# 5ButtonSwitch_ItsyBitsyM0_Rev1_2.net
KiCad netlist of a schematic drawn in EAGLE
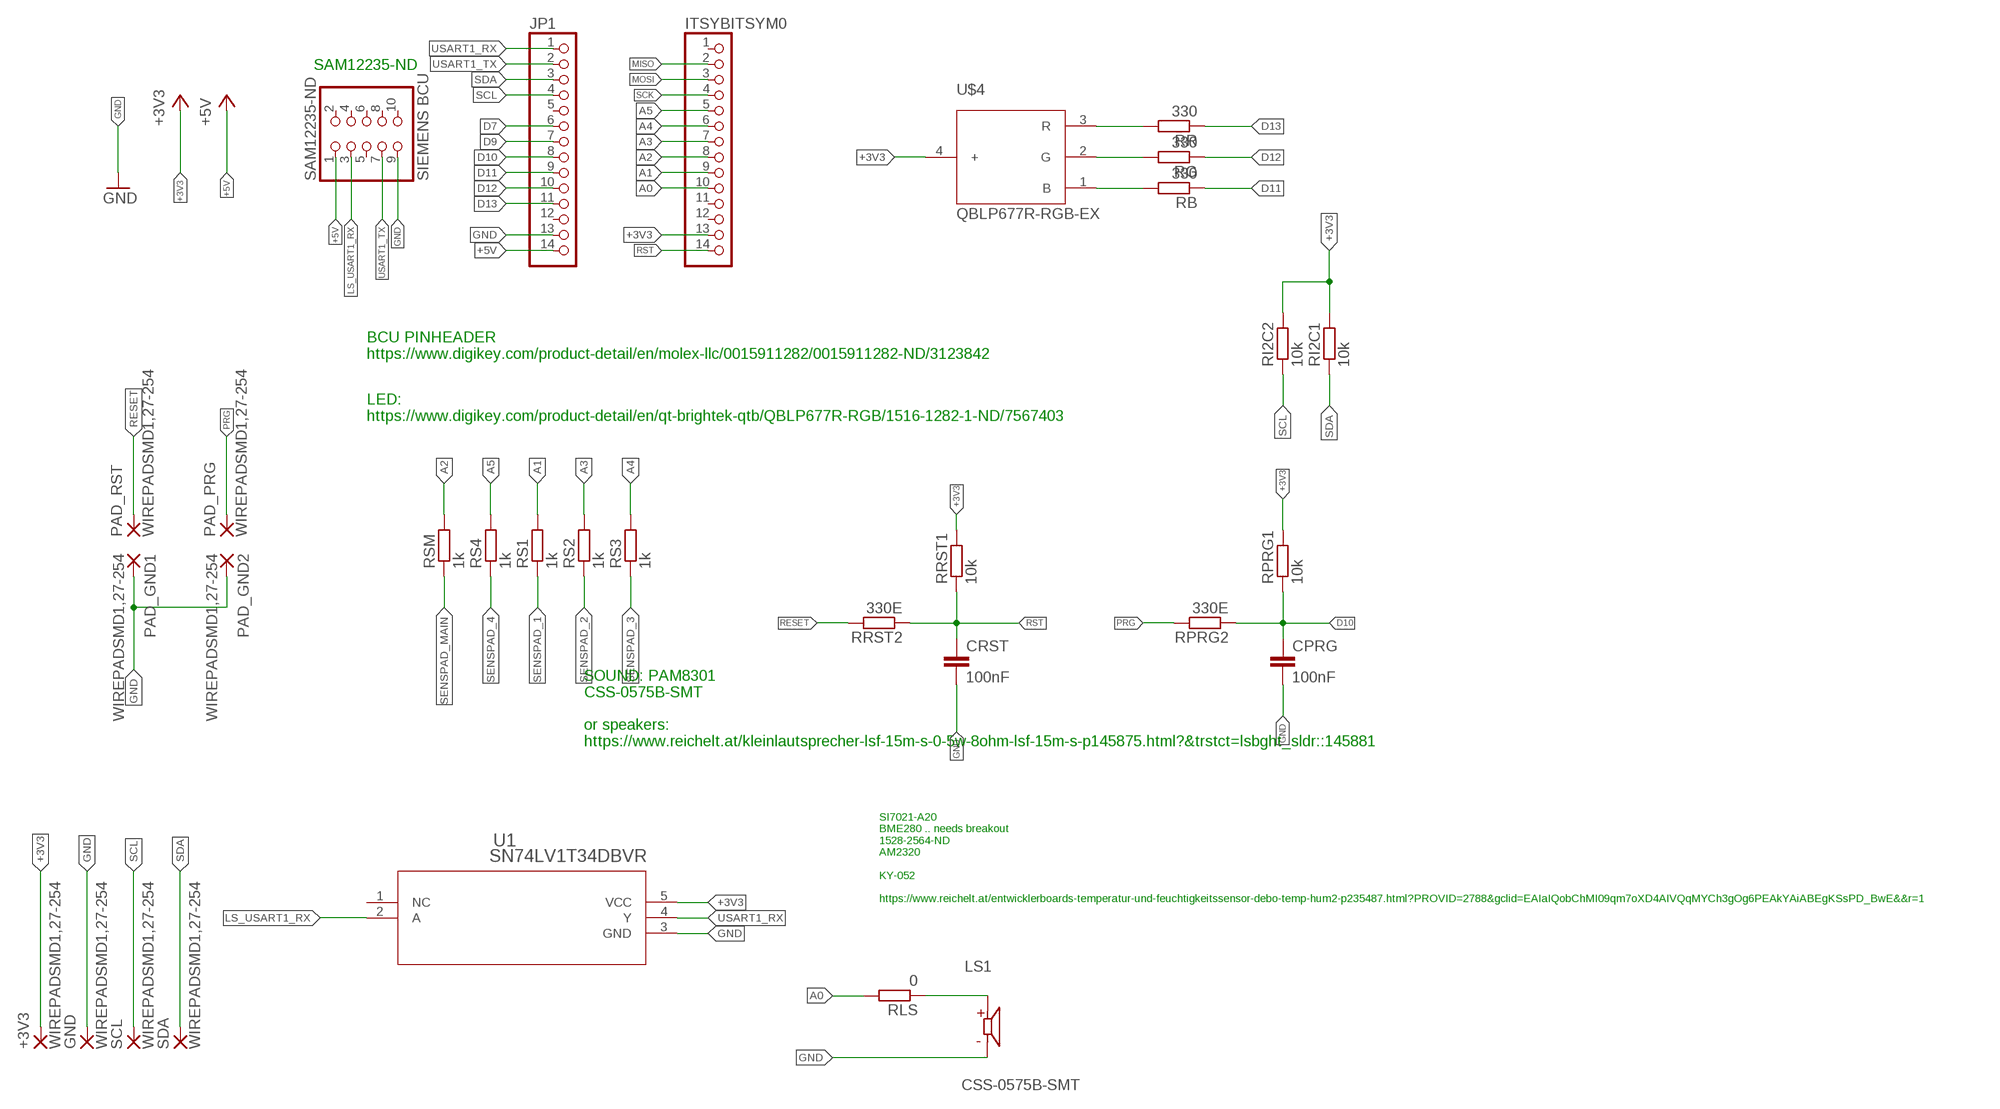
[diagram p0: schematic, sheet 1]

(export (version "E")
  (design (tool "Eeschema 10.0.6"))
  (components
    (comp (ref "+3V3")
      (value "WIREPADSMD1,27-254")
      (footprint "eagle-import:SMD1,27-2,54")
      (libsource (lib "eagle-import") (part "WIREPADSMD1,27-254"))
    )
    (comp (ref "CPRG")
      (value "100nF")
      (footprint "eagle-import:C1206")
      (libsource (lib "eagle-import") (part "C-EUC1206"))
    )
    (comp (ref "CRST")
      (value "100nF")
      (footprint "eagle-import:C1206")
      (libsource (lib "eagle-import") (part "C-EUC1206"))
    )
    (comp (ref "GND")
      (value "WIREPADSMD1,27-254")
      (footprint "eagle-import:SMD1,27-2,54")
      (libsource (lib "eagle-import") (part "WIREPADSMD1,27-254"))
    )
    (comp (ref "ITSYBITSYM0")
      (value "PINHD-1X141X14_SMT")
      (footprint "eagle-import:1X14_SMT")
      (libsource (lib "eagle-import") (part "PINHD-1X141X14_SMT"))
    )
    (comp (ref "JP1")
      (value "PINHD-1X141X14_SMT")
      (footprint "eagle-import:1X14_SMT")
      (libsource (lib "eagle-import") (part "PINHD-1X141X14_SMT"))
    )
    (comp (ref "LS1")
      (value "CSS-0575B-SMT")
      (footprint "eagle-import:CUI_CSS-0575B-SMT")
      (fields
        (field (name "DIGI-KEY_PART_NUMBER") "102-2202-1-ND")
        (field (name "MF") "CUI Inc.")
        (field (name "MP") "CSS-0575B-SMT-TR")
      )
      (libsource (lib "eagle-import") (part "CSS-0575B-SMT"))
    )
    (comp (ref "PAD_GND1")
      (value "WIREPADSMD1,27-254")
      (footprint "eagle-import:SMD1,27-2,54")
      (libsource (lib "eagle-import") (part "WIREPADSMD1,27-254"))
    )
    (comp (ref "PAD_GND2")
      (value "WIREPADSMD1,27-254")
      (footprint "eagle-import:SMD1,27-2,54")
      (libsource (lib "eagle-import") (part "WIREPADSMD1,27-254"))
    )
    (comp (ref "PAD_PRG")
      (value "WIREPADSMD1,27-254")
      (footprint "eagle-import:SMD1,27-2,54")
      (libsource (lib "eagle-import") (part "WIREPADSMD1,27-254"))
    )
    (comp (ref "PAD_RST")
      (value "WIREPADSMD1,27-254")
      (footprint "eagle-import:SMD1,27-2,54")
      (libsource (lib "eagle-import") (part "WIREPADSMD1,27-254"))
    )
    (comp (ref "RB")
      (value "330")
      (footprint "eagle-import:R1206")
      (libsource (lib "eagle-import") (part "R-EU_R1206"))
    )
    (comp (ref "RG")
      (value "330")
      (footprint "eagle-import:R1206")
      (libsource (lib "eagle-import") (part "R-EU_R1206"))
    )
    (comp (ref "RI2C1")
      (value "10k")
      (footprint "eagle-import:R1206")
      (libsource (lib "eagle-import") (part "R-EU_R1206"))
    )
    (comp (ref "RI2C2")
      (value "10k")
      (footprint "eagle-import:R1206")
      (libsource (lib "eagle-import") (part "R-EU_R1206"))
    )
    (comp (ref "RLS")
      (value "0")
      (footprint "eagle-import:R1206")
      (libsource (lib "eagle-import") (part "R-EU_R1206"))
    )
    (comp (ref "RPRG1")
      (value "10k")
      (footprint "eagle-import:R1206")
      (libsource (lib "eagle-import") (part "R-EU_R1206"))
    )
    (comp (ref "RPRG2")
      (value "330E")
      (footprint "eagle-import:R1206")
      (libsource (lib "eagle-import") (part "R-EU_R1206"))
    )
    (comp (ref "RR")
      (value "330")
      (footprint "eagle-import:R1206")
      (libsource (lib "eagle-import") (part "R-EU_R1206"))
    )
    (comp (ref "RRST1")
      (value "10k")
      (footprint "eagle-import:R1206")
      (libsource (lib "eagle-import") (part "R-EU_R1206"))
    )
    (comp (ref "RRST2")
      (value "330E")
      (footprint "eagle-import:R1206")
      (libsource (lib "eagle-import") (part "R-EU_R1206"))
    )
    (comp (ref "RS1")
      (value "1k")
      (footprint "eagle-import:R1206")
      (libsource (lib "eagle-import") (part "R-EU_R1206"))
    )
    (comp (ref "RS2")
      (value "1k")
      (footprint "eagle-import:R1206")
      (libsource (lib "eagle-import") (part "R-EU_R1206"))
    )
    (comp (ref "RS3")
      (value "1k")
      (footprint "eagle-import:R1206")
      (libsource (lib "eagle-import") (part "R-EU_R1206"))
    )
    (comp (ref "RS4")
      (value "1k")
      (footprint "eagle-import:R1206")
      (libsource (lib "eagle-import") (part "R-EU_R1206"))
    )
    (comp (ref "RSM")
      (value "1k")
      (footprint "eagle-import:R1206")
      (libsource (lib "eagle-import") (part "R-EU_R1206"))
    )
    (comp (ref "SAM12235-ND")
      (value "SIEMENS BCU")
      (footprint "eagle-import:2X05SMD")
      (libsource (lib "eagle-import") (part "PINHD-2X5_2.54-SMD"))
    )
    (comp (ref "SCL")
      (value "WIREPADSMD1,27-254")
      (footprint "eagle-import:SMD1,27-2,54")
      (libsource (lib "eagle-import") (part "WIREPADSMD1,27-254"))
    )
    (comp (ref "SDA")
      (value "WIREPADSMD1,27-254")
      (footprint "eagle-import:SMD1,27-2,54")
      (libsource (lib "eagle-import") (part "WIREPADSMD1,27-254"))
    )
    (comp (ref "U$4")
      (value "QBLP677R-RGB-EX")
      (footprint "eagle-import:PLCC4R_EX")
      (libsource (lib "eagle-import") (part "QBLP677R-RGB-EX"))
    )
    (comp (ref "U1")
      (value "SN74LV1T34DBVR")
      (footprint "eagle-import:DBV5")
      (libsource (lib "eagle-import") (part "SN74LV1T34DBVR"))
    )
  )
  (nets
    (net (code "1") (name "+3V3") (class "Default")
      (node (ref "+3V3") (pin "1") (pinfunction "P_1") (pintype "passive"))
      (node (ref "ITSYBITSYM0") (pin "13") (pinfunction "13_13") (pintype "passive"))
      (node (ref "RI2C1") (pin "2") (pinfunction "2_2") (pintype "passive"))
      (node (ref "RI2C2") (pin "2") (pinfunction "2_2") (pintype "passive"))
      (node (ref "RPRG1") (pin "2") (pinfunction "2_2") (pintype "passive"))
      (node (ref "RRST1") (pin "2") (pinfunction "2_2") (pintype "passive"))
      (node (ref "U$4") (pin "4") (pinfunction "+_4") (pintype "power_in"))
      (node (ref "U1") (pin "5") (pinfunction "VCC_5") (pintype "power_in"))
    )
    (net (code "2") (name "+5V") (class "Default")
      (node (ref "JP1") (pin "14") (pinfunction "14_14") (pintype "passive"))
      (node (ref "SAM12235-ND") (pin "1") (pinfunction "1_1") (pintype "passive"))
    )
    (net (code "3") (name "A0") (class "Default")
      (node (ref "ITSYBITSYM0") (pin "10") (pinfunction "10_10") (pintype "passive"))
      (node (ref "RLS") (pin "2") (pinfunction "2_2") (pintype "passive"))
    )
    (net (code "4") (name "A1") (class "Default")
      (node (ref "ITSYBITSYM0") (pin "9") (pinfunction "9_9") (pintype "passive"))
      (node (ref "RS1") (pin "2") (pinfunction "2_2") (pintype "passive"))
    )
    (net (code "5") (name "A2") (class "Default")
      (node (ref "ITSYBITSYM0") (pin "8") (pinfunction "8_8") (pintype "passive"))
      (node (ref "RSM") (pin "2") (pinfunction "2_2") (pintype "passive"))
    )
    (net (code "6") (name "A3") (class "Default")
      (node (ref "ITSYBITSYM0") (pin "7") (pinfunction "7_7") (pintype "passive"))
      (node (ref "RS2") (pin "2") (pinfunction "2_2") (pintype "passive"))
    )
    (net (code "7") (name "A4") (class "Default")
      (node (ref "ITSYBITSYM0") (pin "6") (pinfunction "6_6") (pintype "passive"))
      (node (ref "RS3") (pin "2") (pinfunction "2_2") (pintype "passive"))
    )
    (net (code "8") (name "A5") (class "Default")
      (node (ref "ITSYBITSYM0") (pin "5") (pinfunction "5_5") (pintype "passive"))
      (node (ref "RS4") (pin "2") (pinfunction "2_2") (pintype "passive"))
    )
    (net (code "9") (name "D7") (class "Default")
      (node (ref "JP1") (pin "6") (pinfunction "6_6") (pintype "passive"))
    )
    (net (code "10") (name "D9") (class "Default")
      (node (ref "JP1") (pin "7") (pinfunction "7_7") (pintype "passive"))
    )
    (net (code "11") (name "D10") (class "Default")
      (node (ref "CPRG") (pin "1") (pinfunction "1_1") (pintype "passive"))
      (node (ref "JP1") (pin "8") (pinfunction "8_8") (pintype "passive"))
      (node (ref "RPRG1") (pin "1") (pinfunction "1_1") (pintype "passive"))
      (node (ref "RPRG2") (pin "1") (pinfunction "1_1") (pintype "passive"))
    )
    (net (code "12") (name "D11") (class "Default")
      (node (ref "JP1") (pin "9") (pinfunction "9_9") (pintype "passive"))
      (node (ref "RB") (pin "1") (pinfunction "1_1") (pintype "passive"))
    )
    (net (code "13") (name "D12") (class "Default")
      (node (ref "JP1") (pin "10") (pinfunction "10_10") (pintype "passive"))
      (node (ref "RG") (pin "1") (pinfunction "1_1") (pintype "passive"))
    )
    (net (code "14") (name "D13") (class "Default")
      (node (ref "JP1") (pin "11") (pinfunction "11_11") (pintype "passive"))
      (node (ref "RR") (pin "1") (pinfunction "1_1") (pintype "passive"))
    )
    (net (code "15") (name "GND") (class "Default")
      (node (ref "CPRG") (pin "2") (pinfunction "2_2") (pintype "passive"))
      (node (ref "CRST") (pin "2") (pinfunction "2_2") (pintype "passive"))
      (node (ref "GND") (pin "1") (pinfunction "P_1") (pintype "passive"))
      (node (ref "JP1") (pin "13") (pinfunction "13_13") (pintype "passive"))
      (node (ref "LS1") (pin "2") (pinfunction "N_2") (pintype "passive"))
      (node (ref "PAD_GND1") (pin "1") (pinfunction "P_1") (pintype "passive"))
      (node (ref "PAD_GND2") (pin "1") (pinfunction "P_1") (pintype "passive"))
      (node (ref "SAM12235-ND") (pin "9") (pinfunction "9_9") (pintype "passive"))
      (node (ref "U1") (pin "3") (pinfunction "GND_3") (pintype "power_in"))
    )
    (net (code "16") (name "LS_USART1_RX") (class "Default")
      (node (ref "SAM12235-ND") (pin "3") (pinfunction "3_3") (pintype "passive"))
      (node (ref "U1") (pin "2") (pinfunction "A_2") (pintype "input"))
    )
    (net (code "17") (name "MISO") (class "Default")
      (node (ref "ITSYBITSYM0") (pin "2") (pinfunction "2_2") (pintype "passive"))
    )
    (net (code "18") (name "MOSI") (class "Default")
      (node (ref "ITSYBITSYM0") (pin "3") (pinfunction "3_3") (pintype "passive"))
    )
    (net (code "19") (name "Net-(LS1-P)") (class "Default")
      (node (ref "LS1") (pin "1") (pinfunction "P_1") (pintype "passive"))
      (node (ref "RLS") (pin "1") (pinfunction "1_1") (pintype "passive"))
    )
    (net (code "20") (name "Net-(U$4-B)") (class "Default")
      (node (ref "RB") (pin "2") (pinfunction "2_2") (pintype "passive"))
      (node (ref "U$4") (pin "1") (pinfunction "B_1") (pintype "output"))
    )
    (net (code "21") (name "Net-(U$4-G)") (class "Default")
      (node (ref "RG") (pin "2") (pinfunction "2_2") (pintype "passive"))
      (node (ref "U$4") (pin "2") (pinfunction "G_2") (pintype "output"))
    )
    (net (code "22") (name "Net-(U$4-R)") (class "Default")
      (node (ref "RR") (pin "2") (pinfunction "2_2") (pintype "passive"))
      (node (ref "U$4") (pin "3") (pinfunction "R_3") (pintype "output"))
    )
    (net (code "23") (name "PRG") (class "Default")
      (node (ref "PAD_PRG") (pin "1") (pinfunction "P_1") (pintype "passive"))
      (node (ref "RPRG2") (pin "2") (pinfunction "2_2") (pintype "passive"))
    )
    (net (code "24") (name "RESET") (class "Default")
      (node (ref "PAD_RST") (pin "1") (pinfunction "P_1") (pintype "passive"))
      (node (ref "RRST2") (pin "2") (pinfunction "2_2") (pintype "passive"))
    )
    (net (code "25") (name "RST") (class "Default")
      (node (ref "CRST") (pin "1") (pinfunction "1_1") (pintype "passive"))
      (node (ref "ITSYBITSYM0") (pin "14") (pinfunction "14_14") (pintype "passive"))
      (node (ref "RRST1") (pin "1") (pinfunction "1_1") (pintype "passive"))
      (node (ref "RRST2") (pin "1") (pinfunction "1_1") (pintype "passive"))
    )
    (net (code "26") (name "SCK") (class "Default")
      (node (ref "ITSYBITSYM0") (pin "4") (pinfunction "4_4") (pintype "passive"))
    )
    (net (code "27") (name "SCL") (class "Default")
      (node (ref "JP1") (pin "4") (pinfunction "4_4") (pintype "passive"))
      (node (ref "RI2C2") (pin "1") (pinfunction "1_1") (pintype "passive"))
      (node (ref "SCL") (pin "1") (pinfunction "P_1") (pintype "passive"))
    )
    (net (code "28") (name "SDA") (class "Default")
      (node (ref "JP1") (pin "3") (pinfunction "3_3") (pintype "passive"))
      (node (ref "RI2C1") (pin "1") (pinfunction "1_1") (pintype "passive"))
      (node (ref "SDA") (pin "1") (pinfunction "P_1") (pintype "passive"))
    )
    (net (code "29") (name "SENSPAD_1") (class "Default")
      (node (ref "RS1") (pin "1") (pinfunction "1_1") (pintype "passive"))
    )
    (net (code "30") (name "SENSPAD_2") (class "Default")
      (node (ref "RS2") (pin "1") (pinfunction "1_1") (pintype "passive"))
    )
    (net (code "31") (name "SENSPAD_3") (class "Default")
      (node (ref "RS3") (pin "1") (pinfunction "1_1") (pintype "passive"))
    )
    (net (code "32") (name "SENSPAD_4") (class "Default")
      (node (ref "RS4") (pin "1") (pinfunction "1_1") (pintype "passive"))
    )
    (net (code "33") (name "SENSPAD_MAIN") (class "Default")
      (node (ref "RSM") (pin "1") (pinfunction "1_1") (pintype "passive"))
    )
    (net (code "34") (name "USART1_RX") (class "Default")
      (node (ref "JP1") (pin "1") (pinfunction "1_1") (pintype "passive"))
      (node (ref "U1") (pin "4") (pinfunction "Y_4") (pintype "output"))
    )
    (net (code "35") (name "USART1_TX") (class "Default")
      (node (ref "JP1") (pin "2") (pinfunction "2_2") (pintype "passive"))
      (node (ref "SAM12235-ND") (pin "7") (pinfunction "7_7") (pintype "passive"))
    )
    (net (code "36") (name "unconnected-(ITSYBITSYM0-Pad1)") (class "Default")
      (node (ref "ITSYBITSYM0") (pin "1") (pinfunction "1_1") (pintype "passive"))
    )
    (net (code "37") (name "unconnected-(ITSYBITSYM0-Pad11)") (class "Default")
      (node (ref "ITSYBITSYM0") (pin "11") (pinfunction "11_11") (pintype "passive"))
    )
    (net (code "38") (name "unconnected-(ITSYBITSYM0-Pad12)") (class "Default")
      (node (ref "ITSYBITSYM0") (pin "12") (pinfunction "12_12") (pintype "passive"))
    )
    (net (code "39") (name "unconnected-(JP1-Pad5)") (class "Default")
      (node (ref "JP1") (pin "5") (pinfunction "5_5") (pintype "passive"))
    )
    (net (code "40") (name "unconnected-(JP1-Pad12)") (class "Default")
      (node (ref "JP1") (pin "12") (pinfunction "12_12") (pintype "passive"))
    )
    (net (code "41") (name "unconnected-(SAM12235-ND-Pad2)") (class "Default")
      (node (ref "SAM12235-ND") (pin "2") (pinfunction "2_2") (pintype "passive"))
    )
    (net (code "42") (name "unconnected-(SAM12235-ND-Pad4)") (class "Default")
      (node (ref "SAM12235-ND") (pin "4") (pinfunction "4_4") (pintype "passive"))
    )
    (net (code "43") (name "unconnected-(SAM12235-ND-Pad5)") (class "Default")
      (node (ref "SAM12235-ND") (pin "5") (pinfunction "5_5") (pintype "passive"))
    )
    (net (code "44") (name "unconnected-(SAM12235-ND-Pad6)") (class "Default")
      (node (ref "SAM12235-ND") (pin "6") (pinfunction "6_6") (pintype "passive"))
    )
    (net (code "45") (name "unconnected-(SAM12235-ND-Pad8)") (class "Default")
      (node (ref "SAM12235-ND") (pin "8") (pinfunction "8_8") (pintype "passive"))
    )
    (net (code "46") (name "unconnected-(SAM12235-ND-Pad10)") (class "Default")
      (node (ref "SAM12235-ND") (pin "10") (pinfunction "10_10") (pintype "passive"))
    )
    (net (code "47") (name "unconnected-(U1-NC-Pad1)") (class "Default")
      (node (ref "U1") (pin "1") (pinfunction "NC_1") (pintype "no_connect"))
    )
  )
)
